# fpga00-serdes-power.net
KiCad netlist of a schematic drawn in Altium Designer
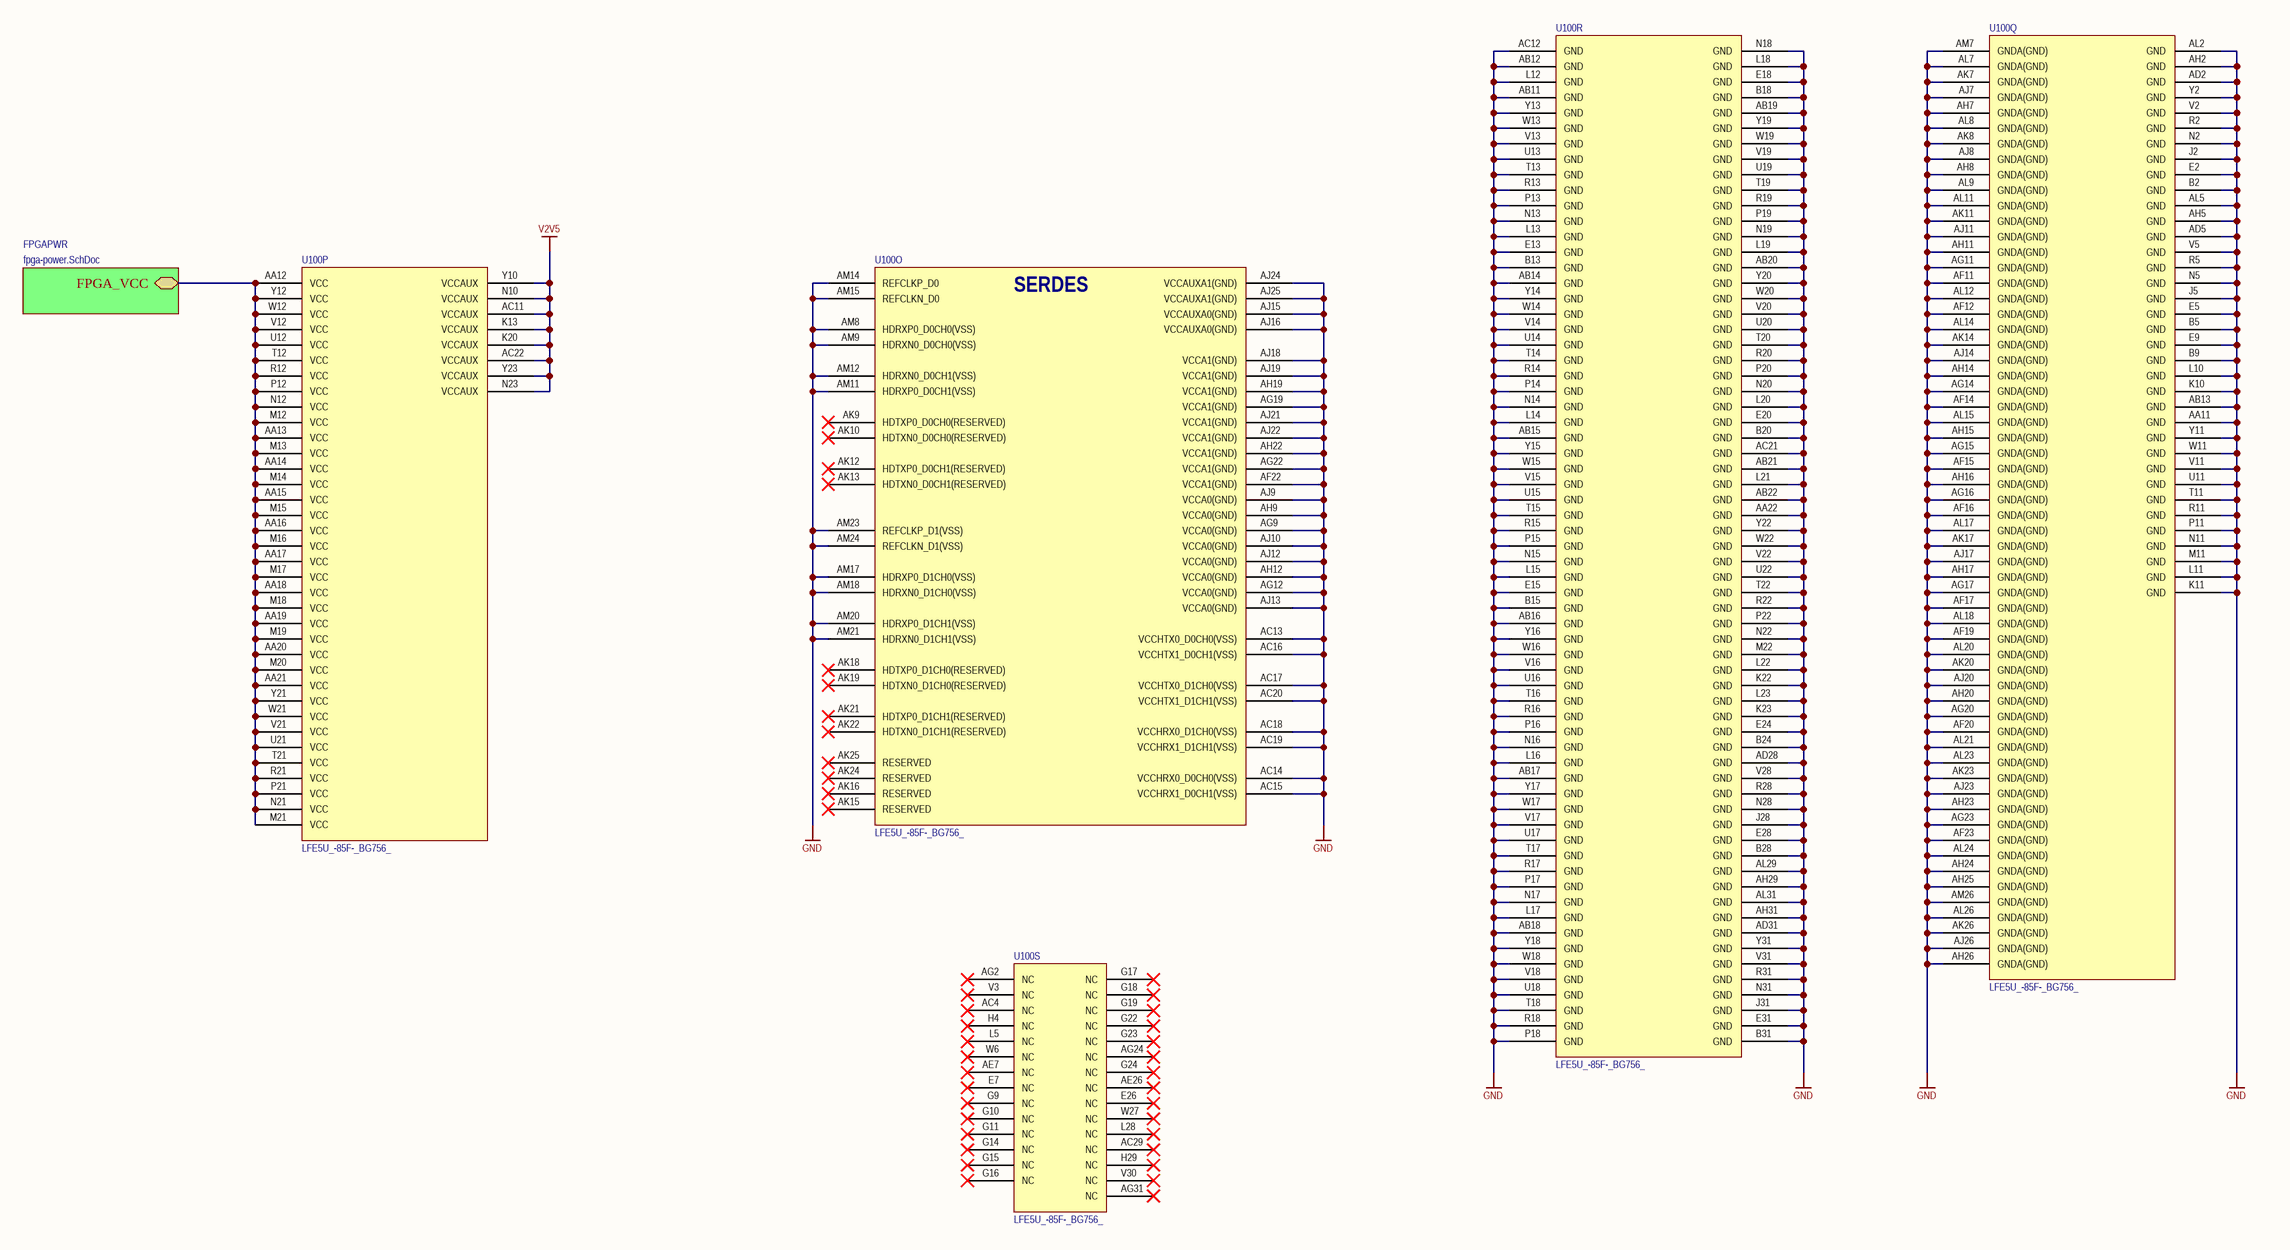
[diagram p0: fpga00-serdes-power.SchDoc]

(export (version "E")
  (design (tool "Eeschema 10.0.6"))
  (components
    (comp (ref "U100")
      (value "LFE5U_-85F-_BG756_")
      (footprint "lattice:caBGA756")
      (description "ECP5 FPGA, 85k LUT, 756-caBGA")
      (fields (field (name "MANUFACTURER") "Lattice Semiconductor"))
      (libsource (lib "lattice") (part "LFE5U_-85F-_BG756_"))
    )
  )
  (nets
    (net (code "1") (name "/FPGA_VCC") (class "Default")
      (node (ref "U100") (pin "AA12") (pinfunction "VCC_AA12") (pintype "power_in"))
      (node (ref "U100") (pin "AA13") (pinfunction "VCC_AA13") (pintype "power_in"))
      (node (ref "U100") (pin "AA14") (pinfunction "VCC_AA14") (pintype "power_in"))
      (node (ref "U100") (pin "AA15") (pinfunction "VCC_AA15") (pintype "power_in"))
      (node (ref "U100") (pin "AA16") (pinfunction "VCC_AA16") (pintype "power_in"))
      (node (ref "U100") (pin "AA17") (pinfunction "VCC_AA17") (pintype "power_in"))
      (node (ref "U100") (pin "AA18") (pinfunction "VCC_AA18") (pintype "power_in"))
      (node (ref "U100") (pin "AA19") (pinfunction "VCC_AA19") (pintype "power_in"))
      (node (ref "U100") (pin "AA20") (pinfunction "VCC_AA20") (pintype "power_in"))
      (node (ref "U100") (pin "AA21") (pinfunction "VCC_AA21") (pintype "power_in"))
      (node (ref "U100") (pin "M12") (pinfunction "VCC_M12") (pintype "power_in"))
      (node (ref "U100") (pin "M13") (pinfunction "VCC_M13") (pintype "power_in"))
      (node (ref "U100") (pin "M14") (pinfunction "VCC_M14") (pintype "power_in"))
      (node (ref "U100") (pin "M15") (pinfunction "VCC_M15") (pintype "power_in"))
      (node (ref "U100") (pin "M16") (pinfunction "VCC_M16") (pintype "power_in"))
      (node (ref "U100") (pin "M17") (pinfunction "VCC_M17") (pintype "power_in"))
      (node (ref "U100") (pin "M18") (pinfunction "VCC_M18") (pintype "power_in"))
      (node (ref "U100") (pin "M19") (pinfunction "VCC_M19") (pintype "power_in"))
      (node (ref "U100") (pin "M20") (pinfunction "VCC_M20") (pintype "power_in"))
      (node (ref "U100") (pin "M21") (pinfunction "VCC_M21") (pintype "power_in"))
      (node (ref "U100") (pin "N12") (pinfunction "VCC_N12") (pintype "power_in"))
      (node (ref "U100") (pin "N21") (pinfunction "VCC_N21") (pintype "power_in"))
      (node (ref "U100") (pin "P12") (pinfunction "VCC_P12") (pintype "power_in"))
      (node (ref "U100") (pin "P21") (pinfunction "VCC_P21") (pintype "power_in"))
      (node (ref "U100") (pin "R12") (pinfunction "VCC_R12") (pintype "power_in"))
      (node (ref "U100") (pin "R21") (pinfunction "VCC_R21") (pintype "power_in"))
      (node (ref "U100") (pin "T12") (pinfunction "VCC_T12") (pintype "power_in"))
      (node (ref "U100") (pin "T21") (pinfunction "VCC_T21") (pintype "power_in"))
      (node (ref "U100") (pin "U12") (pinfunction "VCC_U12") (pintype "power_in"))
      (node (ref "U100") (pin "U21") (pinfunction "VCC_U21") (pintype "power_in"))
      (node (ref "U100") (pin "V12") (pinfunction "VCC_V12") (pintype "power_in"))
      (node (ref "U100") (pin "V21") (pinfunction "VCC_V21") (pintype "power_in"))
      (node (ref "U100") (pin "W12") (pinfunction "VCC_W12") (pintype "power_in"))
      (node (ref "U100") (pin "W21") (pinfunction "VCC_W21") (pintype "power_in"))
      (node (ref "U100") (pin "Y12") (pinfunction "VCC_Y12") (pintype "power_in"))
      (node (ref "U100") (pin "Y21") (pinfunction "VCC_Y21") (pintype "power_in"))
    )
    (net (code "2") (name "GND") (class "Default")
      (node (ref "U100") (pin "AA11") (pinfunction "GND_AA11") (pintype "power_in"))
      (node (ref "U100") (pin "AA22") (pinfunction "GND_AA22") (pintype "power_in"))
      (node (ref "U100") (pin "AB11") (pinfunction "GND_AB11") (pintype "power_in"))
      (node (ref "U100") (pin "AB12") (pinfunction "GND_AB12") (pintype "power_in"))
      (node (ref "U100") (pin "AB13") (pinfunction "GND_AB13") (pintype "power_in"))
      (node (ref "U100") (pin "AB14") (pinfunction "GND_AB14") (pintype "power_in"))
      (node (ref "U100") (pin "AB15") (pinfunction "GND_AB15") (pintype "power_in"))
      (node (ref "U100") (pin "AB16") (pinfunction "GND_AB16") (pintype "power_in"))
      (node (ref "U100") (pin "AB17") (pinfunction "GND_AB17") (pintype "power_in"))
      (node (ref "U100") (pin "AB18") (pinfunction "GND_AB18") (pintype "power_in"))
      (node (ref "U100") (pin "AB19") (pinfunction "GND_AB19") (pintype "power_in"))
      (node (ref "U100") (pin "AB20") (pinfunction "GND_AB20") (pintype "power_in"))
      (node (ref "U100") (pin "AB21") (pinfunction "GND_AB21") (pintype "power_in"))
      (node (ref "U100") (pin "AB22") (pinfunction "GND_AB22") (pintype "power_in"))
      (node (ref "U100") (pin "AC12") (pinfunction "GND_AC12") (pintype "power_in"))
      (node (ref "U100") (pin "AC13") (pinfunction "VCCHTX0_D0CH0(VSS)_AC13") (pintype "power_in"))
      (node (ref "U100") (pin "AC14") (pinfunction "VCCHRX0_D0CH0(VSS)_AC14") (pintype "power_in"))
      (node (ref "U100") (pin "AC15") (pinfunction "VCCHRX1_D0CH1(VSS)_AC15") (pintype "power_in"))
      (node (ref "U100") (pin "AC16") (pinfunction "VCCHTX1_D0CH1(VSS)_AC16") (pintype "power_in"))
      (node (ref "U100") (pin "AC17") (pinfunction "VCCHTX0_D1CH0(VSS)_AC17") (pintype "power_in"))
      (node (ref "U100") (pin "AC18") (pinfunction "VCCHRX0_D1CH0(VSS)_AC18") (pintype "power_in"))
      (node (ref "U100") (pin "AC19") (pinfunction "VCCHRX1_D1CH1(VSS)_AC19") (pintype "power_in"))
      (node (ref "U100") (pin "AC20") (pinfunction "VCCHTX1_D1CH1(VSS)_AC20") (pintype "power_in"))
      (node (ref "U100") (pin "AC21") (pinfunction "GND_AC21") (pintype "power_in"))
      (node (ref "U100") (pin "AD2") (pinfunction "GND_AD2") (pintype "power_in"))
      (node (ref "U100") (pin "AD28") (pinfunction "GND_AD28") (pintype "power_in"))
      (node (ref "U100") (pin "AD31") (pinfunction "GND_AD31") (pintype "power_in"))
      (node (ref "U100") (pin "AD5") (pinfunction "GND_AD5") (pintype "power_in"))
      (node (ref "U100") (pin "AF11") (pinfunction "GNDA(GND)_AF11") (pintype "power_in"))
      (node (ref "U100") (pin "AF12") (pinfunction "GNDA(GND)_AF12") (pintype "power_in"))
      (node (ref "U100") (pin "AF14") (pinfunction "GNDA(GND)_AF14") (pintype "power_in"))
      (node (ref "U100") (pin "AF15") (pinfunction "GNDA(GND)_AF15") (pintype "power_in"))
      (node (ref "U100") (pin "AF16") (pinfunction "GNDA(GND)_AF16") (pintype "power_in"))
      (node (ref "U100") (pin "AF17") (pinfunction "GNDA(GND)_AF17") (pintype "power_in"))
      (node (ref "U100") (pin "AF19") (pinfunction "GNDA(GND)_AF19") (pintype "power_in"))
      (node (ref "U100") (pin "AF20") (pinfunction "GNDA(GND)_AF20") (pintype "power_in"))
      (node (ref "U100") (pin "AF22") (pinfunction "VCCA1(GND)_AF22") (pintype "power_in"))
      (node (ref "U100") (pin "AF23") (pinfunction "GNDA(GND)_AF23") (pintype "power_in"))
      (node (ref "U100") (pin "AG11") (pinfunction "GNDA(GND)_AG11") (pintype "power_in"))
      (node (ref "U100") (pin "AG12") (pinfunction "VCCA0(GND)_AG12") (pintype "power_in"))
      (node (ref "U100") (pin "AG14") (pinfunction "GNDA(GND)_AG14") (pintype "power_in"))
      (node (ref "U100") (pin "AG15") (pinfunction "GNDA(GND)_AG15") (pintype "power_in"))
      (node (ref "U100") (pin "AG16") (pinfunction "GNDA(GND)_AG16") (pintype "power_in"))
      (node (ref "U100") (pin "AG17") (pinfunction "GNDA(GND)_AG17") (pintype "power_in"))
      (node (ref "U100") (pin "AG19") (pinfunction "VCCA1(GND)_AG19") (pintype "power_in"))
      (node (ref "U100") (pin "AG20") (pinfunction "GNDA(GND)_AG20") (pintype "power_in"))
      (node (ref "U100") (pin "AG22") (pinfunction "VCCA1(GND)_AG22") (pintype "power_in"))
      (node (ref "U100") (pin "AG23") (pinfunction "GNDA(GND)_AG23") (pintype "power_in"))
      (node (ref "U100") (pin "AG9") (pinfunction "VCCA0(GND)_AG9") (pintype "power_in"))
      (node (ref "U100") (pin "AH11") (pinfunction "GNDA(GND)_AH11") (pintype "power_in"))
      (node (ref "U100") (pin "AH12") (pinfunction "VCCA0(GND)_AH12") (pintype "power_in"))
      (node (ref "U100") (pin "AH14") (pinfunction "GNDA(GND)_AH14") (pintype "power_in"))
      (node (ref "U100") (pin "AH15") (pinfunction "GNDA(GND)_AH15") (pintype "power_in"))
      (node (ref "U100") (pin "AH16") (pinfunction "GNDA(GND)_AH16") (pintype "power_in"))
      (node (ref "U100") (pin "AH17") (pinfunction "GNDA(GND)_AH17") (pintype "power_in"))
      (node (ref "U100") (pin "AH19") (pinfunction "VCCA1(GND)_AH19") (pintype "power_in"))
      (node (ref "U100") (pin "AH2") (pinfunction "GND_AH2") (pintype "power_in"))
      (node (ref "U100") (pin "AH20") (pinfunction "GNDA(GND)_AH20") (pintype "power_in"))
      (node (ref "U100") (pin "AH22") (pinfunction "VCCA1(GND)_AH22") (pintype "power_in"))
      (node (ref "U100") (pin "AH23") (pinfunction "GNDA(GND)_AH23") (pintype "power_in"))
      (node (ref "U100") (pin "AH24") (pinfunction "GNDA(GND)_AH24") (pintype "power_in"))
      (node (ref "U100") (pin "AH25") (pinfunction "GNDA(GND)_AH25") (pintype "power_in"))
      (node (ref "U100") (pin "AH26") (pinfunction "GNDA(GND)_AH26") (pintype "power_in"))
      (node (ref "U100") (pin "AH29") (pinfunction "GND_AH29") (pintype "power_in"))
      (node (ref "U100") (pin "AH31") (pinfunction "GND_AH31") (pintype "power_in"))
      (node (ref "U100") (pin "AH5") (pinfunction "GND_AH5") (pintype "power_in"))
      (node (ref "U100") (pin "AH7") (pinfunction "GNDA(GND)_AH7") (pintype "power_in"))
      (node (ref "U100") (pin "AH8") (pinfunction "GNDA(GND)_AH8") (pintype "power_in"))
      (node (ref "U100") (pin "AH9") (pinfunction "VCCA0(GND)_AH9") (pintype "power_in"))
      (node (ref "U100") (pin "AJ10") (pinfunction "VCCA0(GND)_AJ10") (pintype "power_in"))
      (node (ref "U100") (pin "AJ11") (pinfunction "GNDA(GND)_AJ11") (pintype "power_in"))
      (node (ref "U100") (pin "AJ12") (pinfunction "VCCA0(GND)_AJ12") (pintype "power_in"))
      (node (ref "U100") (pin "AJ13") (pinfunction "VCCA0(GND)_AJ13") (pintype "power_in"))
      (node (ref "U100") (pin "AJ14") (pinfunction "GNDA(GND)_AJ14") (pintype "power_in"))
      (node (ref "U100") (pin "AJ15") (pinfunction "VCCAUXA0(GND)_AJ15") (pintype "power_in"))
      (node (ref "U100") (pin "AJ16") (pinfunction "VCCAUXA0(GND)_AJ16") (pintype "power_in"))
      (node (ref "U100") (pin "AJ17") (pinfunction "GNDA(GND)_AJ17") (pintype "power_in"))
      (node (ref "U100") (pin "AJ18") (pinfunction "VCCA1(GND)_AJ18") (pintype "power_in"))
      (node (ref "U100") (pin "AJ19") (pinfunction "VCCA1(GND)_AJ19") (pintype "power_in"))
      (node (ref "U100") (pin "AJ20") (pinfunction "GNDA(GND)_AJ20") (pintype "power_in"))
      (node (ref "U100") (pin "AJ21") (pinfunction "VCCA1(GND)_AJ21") (pintype "power_in"))
      (node (ref "U100") (pin "AJ22") (pinfunction "VCCA1(GND)_AJ22") (pintype "power_in"))
      (node (ref "U100") (pin "AJ23") (pinfunction "GNDA(GND)_AJ23") (pintype "power_in"))
      (node (ref "U100") (pin "AJ24") (pinfunction "VCCAUXA1(GND)_AJ24") (pintype "power_in"))
      (node (ref "U100") (pin "AJ25") (pinfunction "VCCAUXA1(GND)_AJ25") (pintype "power_in"))
      (node (ref "U100") (pin "AJ26") (pinfunction "GNDA(GND)_AJ26") (pintype "power_in"))
      (node (ref "U100") (pin "AJ7") (pinfunction "GNDA(GND)_AJ7") (pintype "power_in"))
      (node (ref "U100") (pin "AJ8") (pinfunction "GNDA(GND)_AJ8") (pintype "power_in"))
      (node (ref "U100") (pin "AJ9") (pinfunction "VCCA0(GND)_AJ9") (pintype "power_in"))
      (node (ref "U100") (pin "AK11") (pinfunction "GNDA(GND)_AK11") (pintype "power_in"))
      (node (ref "U100") (pin "AK14") (pinfunction "GNDA(GND)_AK14") (pintype "power_in"))
      (node (ref "U100") (pin "AK17") (pinfunction "GNDA(GND)_AK17") (pintype "power_in"))
      (node (ref "U100") (pin "AK20") (pinfunction "GNDA(GND)_AK20") (pintype "power_in"))
      (node (ref "U100") (pin "AK23") (pinfunction "GNDA(GND)_AK23") (pintype "power_in"))
      (node (ref "U100") (pin "AK26") (pinfunction "GNDA(GND)_AK26") (pintype "power_in"))
      (node (ref "U100") (pin "AK7") (pinfunction "GNDA(GND)_AK7") (pintype "power_in"))
      (node (ref "U100") (pin "AK8") (pinfunction "GNDA(GND)_AK8") (pintype "power_in"))
      (node (ref "U100") (pin "AL11") (pinfunction "GNDA(GND)_AL11") (pintype "power_in"))
      (node (ref "U100") (pin "AL12") (pinfunction "GNDA(GND)_AL12") (pintype "power_in"))
      (node (ref "U100") (pin "AL14") (pinfunction "GNDA(GND)_AL14") (pintype "power_in"))
      (node (ref "U100") (pin "AL15") (pinfunction "GNDA(GND)_AL15") (pintype "power_in"))
      (node (ref "U100") (pin "AL17") (pinfunction "GNDA(GND)_AL17") (pintype "power_in"))
      (node (ref "U100") (pin "AL18") (pinfunction "GNDA(GND)_AL18") (pintype "power_in"))
      (node (ref "U100") (pin "AL2") (pinfunction "GND_AL2") (pintype "power_in"))
      (node (ref "U100") (pin "AL20") (pinfunction "GNDA(GND)_AL20") (pintype "power_in"))
      (node (ref "U100") (pin "AL21") (pinfunction "GNDA(GND)_AL21") (pintype "power_in"))
      (node (ref "U100") (pin "AL23") (pinfunction "GNDA(GND)_AL23") (pintype "power_in"))
      (node (ref "U100") (pin "AL24") (pinfunction "GNDA(GND)_AL24") (pintype "power_in"))
      (node (ref "U100") (pin "AL26") (pinfunction "GNDA(GND)_AL26") (pintype "power_in"))
      (node (ref "U100") (pin "AL29") (pinfunction "GND_AL29") (pintype "power_in"))
      (node (ref "U100") (pin "AL31") (pinfunction "GND_AL31") (pintype "power_in"))
      (node (ref "U100") (pin "AL5") (pinfunction "GND_AL5") (pintype "power_in"))
      (node (ref "U100") (pin "AL7") (pinfunction "GNDA(GND)_AL7") (pintype "power_in"))
      (node (ref "U100") (pin "AL8") (pinfunction "GNDA(GND)_AL8") (pintype "power_in"))
      (node (ref "U100") (pin "AL9") (pinfunction "GNDA(GND)_AL9") (pintype "power_in"))
      (node (ref "U100") (pin "AM11") (pinfunction "HDRXP0_D0CH1(VSS)_AM11") (pintype "passive"))
      (node (ref "U100") (pin "AM12") (pinfunction "HDRXN0_D0CH1(VSS)_AM12") (pintype "passive"))
      (node (ref "U100") (pin "AM14") (pinfunction "REFCLKP_D0_AM14") (pintype "passive"))
      (node (ref "U100") (pin "AM15") (pinfunction "REFCLKN_D0_AM15") (pintype "passive"))
      (node (ref "U100") (pin "AM17") (pinfunction "HDRXP0_D1CH0(VSS)_AM17") (pintype "passive"))
      (node (ref "U100") (pin "AM18") (pinfunction "HDRXN0_D1CH0(VSS)_AM18") (pintype "passive"))
      (node (ref "U100") (pin "AM20") (pinfunction "HDRXP0_D1CH1(VSS)_AM20") (pintype "passive"))
      (node (ref "U100") (pin "AM21") (pinfunction "HDRXN0_D1CH1(VSS)_AM21") (pintype "passive"))
      (node (ref "U100") (pin "AM23") (pinfunction "REFCLKP_D1(VSS)_AM23") (pintype "passive"))
      (node (ref "U100") (pin "AM24") (pinfunction "REFCLKN_D1(VSS)_AM24") (pintype "passive"))
      (node (ref "U100") (pin "AM26") (pinfunction "GNDA(GND)_AM26") (pintype "power_in"))
      (node (ref "U100") (pin "AM7") (pinfunction "GNDA(GND)_AM7") (pintype "power_in"))
      (node (ref "U100") (pin "AM8") (pinfunction "HDRXP0_D0CH0(VSS)_AM8") (pintype "passive"))
      (node (ref "U100") (pin "AM9") (pinfunction "HDRXN0_D0CH0(VSS)_AM9") (pintype "passive"))
      (node (ref "U100") (pin "B13") (pinfunction "GND_B13") (pintype "power_in"))
      (node (ref "U100") (pin "B15") (pinfunction "GND_B15") (pintype "power_in"))
      (node (ref "U100") (pin "B18") (pinfunction "GND_B18") (pintype "power_in"))
      (node (ref "U100") (pin "B2") (pinfunction "GND_B2") (pintype "power_in"))
      (node (ref "U100") (pin "B20") (pinfunction "GND_B20") (pintype "power_in"))
      (node (ref "U100") (pin "B24") (pinfunction "GND_B24") (pintype "power_in"))
      (node (ref "U100") (pin "B28") (pinfunction "GND_B28") (pintype "power_in"))
      (node (ref "U100") (pin "B31") (pinfunction "GND_B31") (pintype "power_in"))
      (node (ref "U100") (pin "B5") (pinfunction "GND_B5") (pintype "power_in"))
      (node (ref "U100") (pin "B9") (pinfunction "GND_B9") (pintype "power_in"))
      (node (ref "U100") (pin "E13") (pinfunction "GND_E13") (pintype "power_in"))
      (node (ref "U100") (pin "E15") (pinfunction "GND_E15") (pintype "power_in"))
      (node (ref "U100") (pin "E18") (pinfunction "GND_E18") (pintype "power_in"))
      (node (ref "U100") (pin "E2") (pinfunction "GND_E2") (pintype "power_in"))
      (node (ref "U100") (pin "E20") (pinfunction "GND_E20") (pintype "power_in"))
      (node (ref "U100") (pin "E24") (pinfunction "GND_E24") (pintype "power_in"))
      (node (ref "U100") (pin "E28") (pinfunction "GND_E28") (pintype "power_in"))
      (node (ref "U100") (pin "E31") (pinfunction "GND_E31") (pintype "power_in"))
      (node (ref "U100") (pin "E5") (pinfunction "GND_E5") (pintype "power_in"))
      (node (ref "U100") (pin "E9") (pinfunction "GND_E9") (pintype "power_in"))
      (node (ref "U100") (pin "J2") (pinfunction "GND_J2") (pintype "power_in"))
      (node (ref "U100") (pin "J28") (pinfunction "GND_J28") (pintype "power_in"))
      (node (ref "U100") (pin "J31") (pinfunction "GND_J31") (pintype "power_in"))
      (node (ref "U100") (pin "J5") (pinfunction "GND_J5") (pintype "power_in"))
      (node (ref "U100") (pin "K10") (pinfunction "GND_K10") (pintype "power_in"))
      (node (ref "U100") (pin "K11") (pinfunction "GND_K11") (pintype "power_in"))
      (node (ref "U100") (pin "K22") (pinfunction "GND_K22") (pintype "power_in"))
      (node (ref "U100") (pin "K23") (pinfunction "GND_K23") (pintype "power_in"))
      (node (ref "U100") (pin "L10") (pinfunction "GND_L10") (pintype "power_in"))
      (node (ref "U100") (pin "L11") (pinfunction "GND_L11") (pintype "power_in"))
      (node (ref "U100") (pin "L12") (pinfunction "GND_L12") (pintype "power_in"))
      (node (ref "U100") (pin "L13") (pinfunction "GND_L13") (pintype "power_in"))
      (node (ref "U100") (pin "L14") (pinfunction "GND_L14") (pintype "power_in"))
      (node (ref "U100") (pin "L15") (pinfunction "GND_L15") (pintype "power_in"))
      (node (ref "U100") (pin "L16") (pinfunction "GND_L16") (pintype "power_in"))
      (node (ref "U100") (pin "L17") (pinfunction "GND_L17") (pintype "power_in"))
      (node (ref "U100") (pin "L18") (pinfunction "GND_L18") (pintype "power_in"))
      (node (ref "U100") (pin "L19") (pinfunction "GND_L19") (pintype "power_in"))
      (node (ref "U100") (pin "L20") (pinfunction "GND_L20") (pintype "power_in"))
      (node (ref "U100") (pin "L21") (pinfunction "GND_L21") (pintype "power_in"))
      (node (ref "U100") (pin "L22") (pinfunction "GND_L22") (pintype "power_in"))
      (node (ref "U100") (pin "L23") (pinfunction "GND_L23") (pintype "power_in"))
      (node (ref "U100") (pin "M11") (pinfunction "GND_M11") (pintype "power_in"))
      (node (ref "U100") (pin "M22") (pinfunction "GND_M22") (pintype "power_in"))
      (node (ref "U100") (pin "N11") (pinfunction "GND_N11") (pintype "power_in"))
      (node (ref "U100") (pin "N13") (pinfunction "GND_N13") (pintype "power_in"))
      (node (ref "U100") (pin "N14") (pinfunction "GND_N14") (pintype "power_in"))
      (node (ref "U100") (pin "N15") (pinfunction "GND_N15") (pintype "power_in"))
      (node (ref "U100") (pin "N16") (pinfunction "GND_N16") (pintype "power_in"))
      (node (ref "U100") (pin "N17") (pinfunction "GND_N17") (pintype "power_in"))
      (node (ref "U100") (pin "N18") (pinfunction "GND_N18") (pintype "power_in"))
      (node (ref "U100") (pin "N19") (pinfunction "GND_N19") (pintype "power_in"))
      (node (ref "U100") (pin "N2") (pinfunction "GND_N2") (pintype "power_in"))
      (node (ref "U100") (pin "N20") (pinfunction "GND_N20") (pintype "power_in"))
      (node (ref "U100") (pin "N22") (pinfunction "GND_N22") (pintype "power_in"))
      (node (ref "U100") (pin "N28") (pinfunction "GND_N28") (pintype "power_in"))
      (node (ref "U100") (pin "N31") (pinfunction "GND_N31") (pintype "power_in"))
      (node (ref "U100") (pin "N5") (pinfunction "GND_N5") (pintype "power_in"))
      (node (ref "U100") (pin "P11") (pinfunction "GND_P11") (pintype "power_in"))
      (node (ref "U100") (pin "P13") (pinfunction "GND_P13") (pintype "power_in"))
      (node (ref "U100") (pin "P14") (pinfunction "GND_P14") (pintype "power_in"))
      (node (ref "U100") (pin "P15") (pinfunction "GND_P15") (pintype "power_in"))
      (node (ref "U100") (pin "P16") (pinfunction "GND_P16") (pintype "power_in"))
      (node (ref "U100") (pin "P17") (pinfunction "GND_P17") (pintype "power_in"))
      (node (ref "U100") (pin "P18") (pinfunction "GND_P18") (pintype "power_in"))
      (node (ref "U100") (pin "P19") (pinfunction "GND_P19") (pintype "power_in"))
      (node (ref "U100") (pin "P20") (pinfunction "GND_P20") (pintype "power_in"))
      (node (ref "U100") (pin "P22") (pinfunction "GND_P22") (pintype "power_in"))
      (node (ref "U100") (pin "R11") (pinfunction "GND_R11") (pintype "power_in"))
      (node (ref "U100") (pin "R13") (pinfunction "GND_R13") (pintype "power_in"))
      (node (ref "U100") (pin "R14") (pinfunction "GND_R14") (pintype "power_in"))
      (node (ref "U100") (pin "R15") (pinfunction "GND_R15") (pintype "power_in"))
      (node (ref "U100") (pin "R16") (pinfunction "GND_R16") (pintype "power_in"))
      (node (ref "U100") (pin "R17") (pinfunction "GND_R17") (pintype "power_in"))
      (node (ref "U100") (pin "R18") (pinfunction "GND_R18") (pintype "power_in"))
      (node (ref "U100") (pin "R19") (pinfunction "GND_R19") (pintype "power_in"))
      (node (ref "U100") (pin "R2") (pinfunction "GND_R2") (pintype "power_in"))
      (node (ref "U100") (pin "R20") (pinfunction "GND_R20") (pintype "power_in"))
      (node (ref "U100") (pin "R22") (pinfunction "GND_R22") (pintype "power_in"))
      (node (ref "U100") (pin "R28") (pinfunction "GND_R28") (pintype "power_in"))
      (node (ref "U100") (pin "R31") (pinfunction "GND_R31") (pintype "power_in"))
      (node (ref "U100") (pin "R5") (pinfunction "GND_R5") (pintype "power_in"))
      (node (ref "U100") (pin "T11") (pinfunction "GND_T11") (pintype "power_in"))
      (node (ref "U100") (pin "T13") (pinfunction "GND_T13") (pintype "power_in"))
      (node (ref "U100") (pin "T14") (pinfunction "GND_T14") (pintype "power_in"))
      (node (ref "U100") (pin "T15") (pinfunction "GND_T15") (pintype "power_in"))
      (node (ref "U100") (pin "T16") (pinfunction "GND_T16") (pintype "power_in"))
      (node (ref "U100") (pin "T17") (pinfunction "GND_T17") (pintype "power_in"))
      (node (ref "U100") (pin "T18") (pinfunction "GND_T18") (pintype "power_in"))
      (node (ref "U100") (pin "T19") (pinfunction "GND_T19") (pintype "power_in"))
      (node (ref "U100") (pin "T20") (pinfunction "GND_T20") (pintype "power_in"))
      (node (ref "U100") (pin "T22") (pinfunction "GND_T22") (pintype "power_in"))
      (node (ref "U100") (pin "U11") (pinfunction "GND_U11") (pintype "power_in"))
      (node (ref "U100") (pin "U13") (pinfunction "GND_U13") (pintype "power_in"))
      (node (ref "U100") (pin "U14") (pinfunction "GND_U14") (pintype "power_in"))
      (node (ref "U100") (pin "U15") (pinfunction "GND_U15") (pintype "power_in"))
      (node (ref "U100") (pin "U16") (pinfunction "GND_U16") (pintype "power_in"))
      (node (ref "U100") (pin "U17") (pinfunction "GND_U17") (pintype "power_in"))
      (node (ref "U100") (pin "U18") (pinfunction "GND_U18") (pintype "power_in"))
      (node (ref "U100") (pin "U19") (pinfunction "GND_U19") (pintype "power_in"))
      (node (ref "U100") (pin "U20") (pinfunction "GND_U20") (pintype "power_in"))
      (node (ref "U100") (pin "U22") (pinfunction "GND_U22") (pintype "power_in"))
      (node (ref "U100") (pin "V11") (pinfunction "GND_V11") (pintype "power_in"))
      (node (ref "U100") (pin "V13") (pinfunction "GND_V13") (pintype "power_in"))
      (node (ref "U100") (pin "V14") (pinfunction "GND_V14") (pintype "power_in"))
      (node (ref "U100") (pin "V15") (pinfunction "GND_V15") (pintype "power_in"))
      (node (ref "U100") (pin "V16") (pinfunction "GND_V16") (pintype "power_in"))
      (node (ref "U100") (pin "V17") (pinfunction "GND_V17") (pintype "power_in"))
      (node (ref "U100") (pin "V18") (pinfunction "GND_V18") (pintype "power_in"))
      (node (ref "U100") (pin "V19") (pinfunction "GND_V19") (pintype "power_in"))
      (node (ref "U100") (pin "V2") (pinfunction "GND_V2") (pintype "power_in"))
      (node (ref "U100") (pin "V20") (pinfunction "GND_V20") (pintype "power_in"))
      (node (ref "U100") (pin "V22") (pinfunction "GND_V22") (pintype "power_in"))
      (node (ref "U100") (pin "V28") (pinfunction "GND_V28") (pintype "power_in"))
      (node (ref "U100") (pin "V31") (pinfunction "GND_V31") (pintype "power_in"))
      (node (ref "U100") (pin "V5") (pinfunction "GND_V5") (pintype "power_in"))
      (node (ref "U100") (pin "W11") (pinfunction "GND_W11") (pintype "power_in"))
      (node (ref "U100") (pin "W13") (pinfunction "GND_W13") (pintype "power_in"))
      (node (ref "U100") (pin "W14") (pinfunction "GND_W14") (pintype "power_in"))
      (node (ref "U100") (pin "W15") (pinfunction "GND_W15") (pintype "power_in"))
      (node (ref "U100") (pin "W16") (pinfunction "GND_W16") (pintype "power_in"))
      (node (ref "U100") (pin "W17") (pinfunction "GND_W17") (pintype "power_in"))
      (node (ref "U100") (pin "W18") (pinfunction "GND_W18") (pintype "power_in"))
      (node (ref "U100") (pin "W19") (pinfunction "GND_W19") (pintype "power_in"))
      (node (ref "U100") (pin "W20") (pinfunction "GND_W20") (pintype "power_in"))
      (node (ref "U100") (pin "W22") (pinfunction "GND_W22") (pintype "power_in"))
      (node (ref "U100") (pin "Y11") (pinfunction "GND_Y11") (pintype "power_in"))
      (node (ref "U100") (pin "Y13") (pinfunction "GND_Y13") (pintype "power_in"))
      (node (ref "U100") (pin "Y14") (pinfunction "GND_Y14") (pintype "power_in"))
      (node (ref "U100") (pin "Y15") (pinfunction "GND_Y15") (pintype "power_in"))
      (node (ref "U100") (pin "Y16") (pinfunction "GND_Y16") (pintype "power_in"))
      (node (ref "U100") (pin "Y17") (pinfunction "GND_Y17") (pintype "power_in"))
      (node (ref "U100") (pin "Y18") (pinfunction "GND_Y18") (pintype "power_in"))
      (node (ref "U100") (pin "Y19") (pinfunction "GND_Y19") (pintype "power_in"))
      (node (ref "U100") (pin "Y2") (pinfunction "GND_Y2") (pintype "power_in"))
      (node (ref "U100") (pin "Y20") (pinfunction "GND_Y20") (pintype "power_in"))
      (node (ref "U100") (pin "Y22") (pinfunction "GND_Y22") (pintype "power_in"))
      (node (ref "U100") (pin "Y31") (pinfunction "GND_Y31") (pintype "power_in"))
    )
    (net (code "3") (name "V2V5") (class "Default")
      (node (ref "U100") (pin "AC11") (pinfunction "VCCAUX_AC11") (pintype "power_in"))
      (node (ref "U100") (pin "AC22") (pinfunction "VCCAUX_AC22") (pintype "power_in"))
      (node (ref "U100") (pin "K13") (pinfunction "VCCAUX_K13") (pintype "power_in"))
      (node (ref "U100") (pin "K20") (pinfunction "VCCAUX_K20") (pintype "power_in"))
      (node (ref "U100") (pin "N10") (pinfunction "VCCAUX_N10") (pintype "power_in"))
      (node (ref "U100") (pin "N23") (pinfunction "VCCAUX_N23") (pintype "power_in"))
      (node (ref "U100") (pin "Y10") (pinfunction "VCCAUX_Y10") (pintype "power_in"))
      (node (ref "U100") (pin "Y23") (pinfunction "VCCAUX_Y23") (pintype "power_in"))
    )
    (net (code "4") (name "unconnected-(U100O-HDTXN0_D0CH0(RESERVED)-PadAK10)") (class "Default")
      (node (ref "U100") (pin "AK10") (pinfunction "HDTXN0_D0CH0(RESERVED)_AK10") (pintype "passive+no_connect"))
    )
    (net (code "5") (name "unconnected-(U100O-HDTXN0_D0CH1(RESERVED)-PadAK13)") (class "Default")
      (node (ref "U100") (pin "AK13") (pinfunction "HDTXN0_D0CH1(RESERVED)_AK13") (pintype "passive+no_connect"))
    )
    (net (code "6") (name "unconnected-(U100O-HDTXN0_D1CH0(RESERVED)-PadAK19)") (class "Default")
      (node (ref "U100") (pin "AK19") (pinfunction "HDTXN0_D1CH0(RESERVED)_AK19") (pintype "passive+no_connect"))
    )
    (net (code "7") (name "unconnected-(U100O-HDTXN0_D1CH1(RESERVED)-PadAK22)") (class "Default")
      (node (ref "U100") (pin "AK22") (pinfunction "HDTXN0_D1CH1(RESERVED)_AK22") (pintype "passive+no_connect"))
    )
    (net (code "8") (name "unconnected-(U100O-HDTXP0_D0CH0(RESERVED)-PadAK9)") (class "Default")
      (node (ref "U100") (pin "AK9") (pinfunction "HDTXP0_D0CH0(RESERVED)_AK9") (pintype "passive+no_connect"))
    )
    (net (code "9") (name "unconnected-(U100O-HDTXP0_D0CH1(RESERVED)-PadAK12)") (class "Default")
      (node (ref "U100") (pin "AK12") (pinfunction "HDTXP0_D0CH1(RESERVED)_AK12") (pintype "passive+no_connect"))
    )
    (net (code "10") (name "unconnected-(U100O-HDTXP0_D1CH0(RESERVED)-PadAK18)") (class "Default")
      (node (ref "U100") (pin "AK18") (pinfunction "HDTXP0_D1CH0(RESERVED)_AK18") (pintype "passive+no_connect"))
    )
    (net (code "11") (name "unconnected-(U100O-HDTXP0_D1CH1(RESERVED)-PadAK21)") (class "Default")
      (node (ref "U100") (pin "AK21") (pinfunction "HDTXP0_D1CH1(RESERVED)_AK21") (pintype "passive+no_connect"))
    )
    (net (code "12") (name "unconnected-(U100O-RESERVED-PadAK15)") (class "Default")
      (node (ref "U100") (pin "AK15") (pinfunction "RESERVED_AK15") (pintype "passive+no_connect"))
    )
    (net (code "13") (name "unconnected-(U100O-RESERVED-PadAK16)") (class "Default")
      (node (ref "U100") (pin "AK16") (pinfunction "RESERVED_AK16") (pintype "passive+no_connect"))
    )
    (net (code "14") (name "unconnected-(U100O-RESERVED-PadAK24)") (class "Default")
      (node (ref "U100") (pin "AK24") (pinfunction "RESERVED_AK24") (pintype "passive+no_connect"))
    )
    (net (code "15") (name "unconnected-(U100O-RESERVED-PadAK25)") (class "Default")
      (node (ref "U100") (pin "AK25") (pinfunction "RESERVED_AK25") (pintype "passive+no_connect"))
    )
    (net (code "16") (name "unconnected-(U100S-NC-PadAC4)") (class "Default")
      (node (ref "U100") (pin "AC4") (pinfunction "NC_AC4") (pintype "passive+no_connect"))
    )
    (net (code "17") (name "unconnected-(U100S-NC-PadAC29)") (class "Default")
      (node (ref "U100") (pin "AC29") (pinfunction "NC_AC29") (pintype "passive+no_connect"))
    )
    (net (code "18") (name "unconnected-(U100S-NC-PadAE7)") (class "Default")
      (node (ref "U100") (pin "AE7") (pinfunction "NC_AE7") (pintype "passive+no_connect"))
    )
    (net (code "19") (name "unconnected-(U100S-NC-PadAE26)") (class "Default")
      (node (ref "U100") (pin "AE26") (pinfunction "NC_AE26") (pintype "passive+no_connect"))
    )
    (net (code "20") (name "unconnected-(U100S-NC-PadAG2)") (class "Default")
      (node (ref "U100") (pin "AG2") (pinfunction "NC_AG2") (pintype "passive+no_connect"))
    )
    (net (code "21") (name "unconnected-(U100S-NC-PadAG24)") (class "Default")
      (node (ref "U100") (pin "AG24") (pinfunction "NC_AG24") (pintype "passive+no_connect"))
    )
    (net (code "22") (name "unconnected-(U100S-NC-PadAG31)") (class "Default")
      (node (ref "U100") (pin "AG31") (pinfunction "NC_AG31") (pintype "passive+no_connect"))
    )
    (net (code "23") (name "unconnected-(U100S-NC-PadE7)") (class "Default")
      (node (ref "U100") (pin "E7") (pinfunction "NC_E7") (pintype "passive+no_connect"))
    )
    (net (code "24") (name "unconnected-(U100S-NC-PadE26)") (class "Default")
      (node (ref "U100") (pin "E26") (pinfunction "NC_E26") (pintype "passive+no_connect"))
    )
    (net (code "25") (name "unconnected-(U100S-NC-PadG9)") (class "Default")
      (node (ref "U100") (pin "G9") (pinfunction "NC_G9") (pintype "passive+no_connect"))
    )
    (net (code "26") (name "unconnected-(U100S-NC-PadG10)") (class "Default")
      (node (ref "U100") (pin "G10") (pinfunction "NC_G10") (pintype "passive+no_connect"))
    )
    (net (code "27") (name "unconnected-(U100S-NC-PadG11)") (class "Default")
      (node (ref "U100") (pin "G11") (pinfunction "NC_G11") (pintype "passive+no_connect"))
    )
    (net (code "28") (name "unconnected-(U100S-NC-PadG14)") (class "Default")
      (node (ref "U100") (pin "G14") (pinfunction "NC_G14") (pintype "passive+no_connect"))
    )
    (net (code "29") (name "unconnected-(U100S-NC-PadG15)") (class "Default")
      (node (ref "U100") (pin "G15") (pinfunction "NC_G15") (pintype "passive+no_connect"))
    )
    (net (code "30") (name "unconnected-(U100S-NC-PadG16)") (class "Default")
      (node (ref "U100") (pin "G16") (pinfunction "NC_G16") (pintype "passive+no_connect"))
    )
    (net (code "31") (name "unconnected-(U100S-NC-PadG17)") (class "Default")
      (node (ref "U100") (pin "G17") (pinfunction "NC_G17") (pintype "passive+no_connect"))
    )
    (net (code "32") (name "unconnected-(U100S-NC-PadG18)") (class "Default")
      (node (ref "U100") (pin "G18") (pinfunction "NC_G18") (pintype "passive+no_connect"))
    )
    (net (code "33") (name "unconnected-(U100S-NC-PadG19)") (class "Default")
      (node (ref "U100") (pin "G19") (pinfunction "NC_G19") (pintype "passive+no_connect"))
    )
    (net (code "34") (name "unconnected-(U100S-NC-PadG22)") (class "Default")
      (node (ref "U100") (pin "G22") (pinfunction "NC_G22") (pintype "passive+no_connect"))
    )
    (net (code "35") (name "unconnected-(U100S-NC-PadG23)") (class "Default")
      (node (ref "U100") (pin "G23") (pinfunction "NC_G23") (pintype "passive+no_connect"))
    )
    (net (code "36") (name "unconnected-(U100S-NC-PadG24)") (class "Default")
      (node (ref "U100") (pin "G24") (pinfunction "NC_G24") (pintype "passive+no_connect"))
    )
    (net (code "37") (name "unconnected-(U100S-NC-PadH4)") (class "Default")
      (node (ref "U100") (pin "H4") (pinfunction "NC_H4") (pintype "passive+no_connect"))
    )
    (net (code "38") (name "unconnected-(U100S-NC-PadH29)") (class "Default")
      (node (ref "U100") (pin "H29") (pinfunction "NC_H29") (pintype "passive+no_connect"))
    )
    (net (code "39") (name "unconnected-(U100S-NC-PadL5)") (class "Default")
      (node (ref "U100") (pin "L5") (pinfunction "NC_L5") (pintype "passive+no_connect"))
    )
    (net (code "40") (name "unconnected-(U100S-NC-PadL28)") (class "Default")
      (node (ref "U100") (pin "L28") (pinfunction "NC_L28") (pintype "passive+no_connect"))
    )
    (net (code "41") (name "unconnected-(U100S-NC-PadV3)") (class "Default")
      (node (ref "U100") (pin "V3") (pinfunction "NC_V3") (pintype "passive+no_connect"))
    )
    (net (code "42") (name "unconnected-(U100S-NC-PadV30)") (class "Default")
      (node (ref "U100") (pin "V30") (pinfunction "NC_V30") (pintype "passive+no_connect"))
    )
    (net (code "43") (name "unconnected-(U100S-NC-PadW6)") (class "Default")
      (node (ref "U100") (pin "W6") (pinfunction "NC_W6") (pintype "passive+no_connect"))
    )
    (net (code "44") (name "unconnected-(U100S-NC-PadW27)") (class "Default")
      (node (ref "U100") (pin "W27") (pinfunction "NC_W27") (pintype "passive+no_connect"))
    )
  )
)
